# sensors.net
KiCad netlist of a schematic drawn in Altium Designer
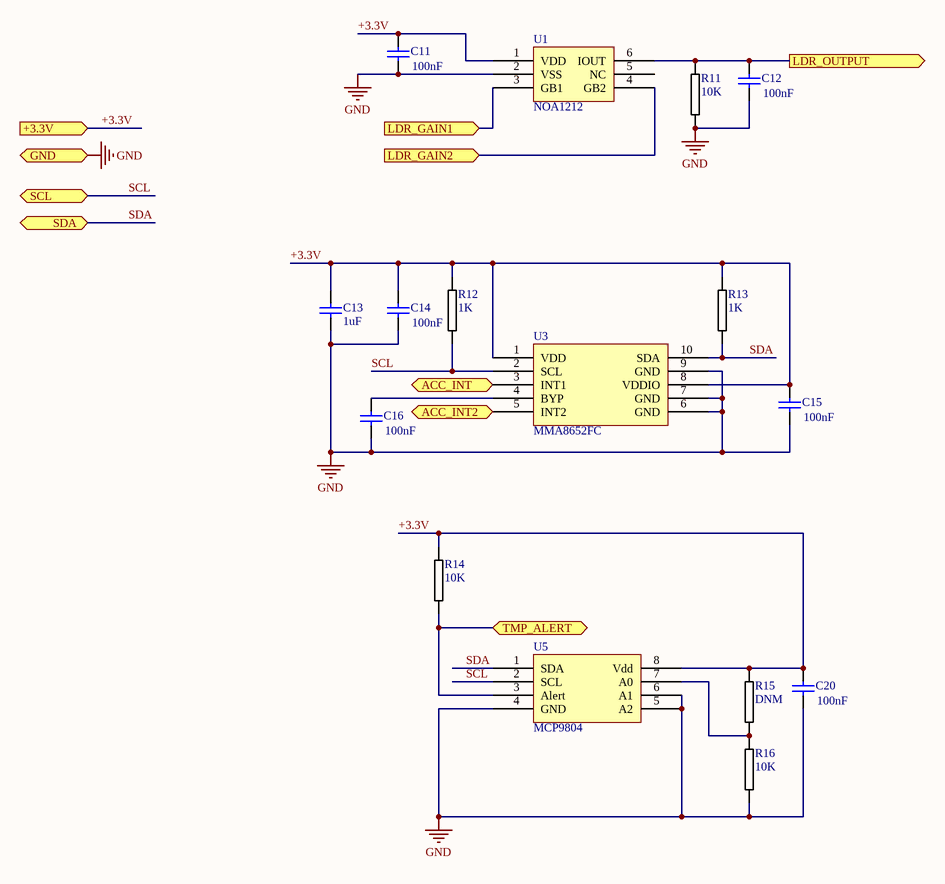
[diagram p0: sensors.SchDoc]

(export (version "E")
  (design (tool "Eeschema 10.0.6"))
  (components
    (comp (ref "C11")
      (value "100nF")
      (footprint "0402C-TBD")
      (description "Capacitor, X7R")
      (libsource (lib "Miscellaneous Devices") (part "Cap"))
    )
    (comp (ref "C12")
      (value "100nF")
      (footprint "0402C-TBD")
      (description "Capacitor, X7R")
      (libsource (lib "Miscellaneous Devices") (part "Cap"))
    )
    (comp (ref "C13")
      (value "1uF")
      (footprint "C0805")
      (description "Capacitor")
      (libsource (lib "Miscellaneous Devices") (part "Cap"))
    )
    (comp (ref "C14")
      (value "100nF")
      (footprint "0402C-TBD")
      (description "Capacitor, X7R")
      (libsource (lib "Miscellaneous Devices") (part "Cap"))
    )
    (comp (ref "C15")
      (value "100nF")
      (footprint "0402C-TBD")
      (description "Capacitor, X7R")
      (libsource (lib "Miscellaneous Devices") (part "Cap"))
    )
    (comp (ref "C16")
      (value "100nF")
      (footprint "0402C-TBD")
      (description "Capacitor, X7R")
      (libsource (lib "Miscellaneous Devices") (part "Cap"))
    )
    (comp (ref "C20")
      (value "100nF")
      (footprint "0402C-TBD")
      (description "Capacitor, X7R")
      (libsource (lib "Miscellaneous Devices") (part "Cap"))
    )
    (comp (ref "R11")
      (value "10K")
      (footprint "0402R-GENERIC")
      (description "RESISTOR 0402 GENERIC")
      (libsource (lib "vh_Altium Library") (part "0402R-GENERIC"))
    )
    (comp (ref "R12")
      (value "1K")
      (footprint "0402R-GENERIC")
      (description "RESISTOR 0402 GENERIC")
      (libsource (lib "vh_Altium Library") (part "0402R-GENERIC"))
    )
    (comp (ref "R13")
      (value "1K")
      (footprint "0402R-GENERIC")
      (description "RESISTOR 0402 GENERIC")
      (libsource (lib "vh_Altium Library") (part "0402R-GENERIC"))
    )
    (comp (ref "R14")
      (value "10K")
      (footprint "0402R-GENERIC")
      (description "RESISTOR 0402 GENERIC")
      (libsource (lib "vh_Altium Library") (part "0402R-GENERIC"))
    )
    (comp (ref "R15")
      (value "DNM")
      (footprint "0402R-GENERIC")
      (description "RESISTOR 0402 GENERIC")
      (libsource (lib "vh_Altium Library") (part "0402R-GENERIC"))
    )
    (comp (ref "R16")
      (value "10K")
      (footprint "0402R-GENERIC")
      (description "RESISTOR 0402 GENERIC")
      (libsource (lib "vh_Altium Library") (part "0402R-GENERIC"))
    )
    (comp (ref "U1") (value "NOA1212") (footprint "NOA1212") (libsource (lib "dell") (part "NOA1212")))
    (comp (ref "U3") (value "MMA8652FC") (footprint "DFN10") (libsource (lib "dell") (part "MMA8652FC")))
    (comp (ref "U5") (value "MCP9804") (footprint "MSOP-MS8_N") (libsource (lib "Schlib1") (part "MCP9804")))
  )
  (nets
    (net (code "1") (name "/+3.3V") (class "Default")
      (node (ref "C11") (pin "2") (pinfunction "2_2") (pintype "passive"))
      (node (ref "C13") (pin "2") (pinfunction "2_2") (pintype "passive"))
      (node (ref "C14") (pin "2") (pinfunction "2_2") (pintype "passive"))
      (node (ref "C15") (pin "2") (pinfunction "2_2") (pintype "passive"))
      (node (ref "C20") (pin "2") (pinfunction "2_2") (pintype "passive"))
      (node (ref "R12") (pin "2") (pintype "passive"))
      (node (ref "R13") (pin "2") (pintype "passive"))
      (node (ref "R14") (pin "2") (pintype "passive"))
      (node (ref "R15") (pin "2") (pintype "passive"))
      (node (ref "U1") (pin "1") (pinfunction "VDD_1") (pintype "passive"))
      (node (ref "U3") (pin "1") (pinfunction "VDD_1") (pintype "passive"))
      (node (ref "U3") (pin "8") (pinfunction "VDDIO_8") (pintype "passive"))
      (node (ref "U5") (pin "8") (pinfunction "Vdd_8") (pintype "passive"))
    )
    (net (code "2") (name "/ACC_INT") (class "Default")
      (node (ref "U3") (pin "3") (pinfunction "INT1_3") (pintype "passive"))
    )
    (net (code "3") (name "/ACC_INT2") (class "Default")
      (node (ref "U3") (pin "5") (pinfunction "INT2_5") (pintype "passive"))
    )
    (net (code "4") (name "/LDR_GAIN1") (class "Default")
      (node (ref "U1") (pin "3") (pinfunction "GB1_3") (pintype "passive"))
    )
    (net (code "5") (name "/LDR_GAIN2") (class "Default")
      (node (ref "U1") (pin "4") (pinfunction "GB2_4") (pintype "passive"))
    )
    (net (code "6") (name "/LDR_OUTPUT") (class "Default")
      (node (ref "C12") (pin "2") (pinfunction "2_2") (pintype "passive"))
      (node (ref "R11") (pin "2") (pintype "passive"))
      (node (ref "U1") (pin "6") (pinfunction "IOUT_6") (pintype "passive"))
    )
    (net (code "7") (name "/SCL") (class "Default")
      (node (ref "R12") (pin "1") (pintype "passive"))
      (node (ref "U3") (pin "2") (pinfunction "SCL_2") (pintype "passive"))
      (node (ref "U5") (pin "2") (pinfunction "SCL_2") (pintype "passive"))
    )
    (net (code "8") (name "/SDA") (class "Default")
      (node (ref "R13") (pin "1") (pintype "passive"))
      (node (ref "U3") (pin "10") (pinfunction "SDA_10") (pintype "passive"))
      (node (ref "U5") (pin "1") (pinfunction "SDA_1") (pintype "passive"))
    )
    (net (code "9") (name "/TMP_ALERT") (class "Default")
      (node (ref "R14") (pin "1") (pintype "passive"))
      (node (ref "U5") (pin "3") (pinfunction "Alert_3") (pintype "passive"))
    )
    (net (code "10") (name "GND") (class "Default")
      (node (ref "C11") (pin "1") (pinfunction "1_1") (pintype "passive"))
      (node (ref "C12") (pin "1") (pinfunction "1_1") (pintype "passive"))
      (node (ref "C13") (pin "1") (pinfunction "1_1") (pintype "passive"))
      (node (ref "C14") (pin "1") (pinfunction "1_1") (pintype "passive"))
      (node (ref "C15") (pin "1") (pinfunction "1_1") (pintype "passive"))
      (node (ref "C16") (pin "1") (pinfunction "1_1") (pintype "passive"))
      (node (ref "C20") (pin "1") (pinfunction "1_1") (pintype "passive"))
      (node (ref "R11") (pin "1") (pintype "passive"))
      (node (ref "R16") (pin "1") (pintype "passive"))
      (node (ref "U1") (pin "2") (pinfunction "VSS_2") (pintype "passive"))
      (node (ref "U3") (pin "6") (pinfunction "GND_6") (pintype "passive"))
      (node (ref "U3") (pin "7") (pinfunction "GND_7") (pintype "passive"))
      (node (ref "U3") (pin "9") (pinfunction "GND_9") (pintype "passive"))
      (node (ref "U5") (pin "4") (pinfunction "GND_4") (pintype "passive"))
      (node (ref "U5") (pin "5") (pinfunction "A2_5") (pintype "passive"))
      (node (ref "U5") (pin "6") (pinfunction "A1_6") (pintype "passive"))
    )
    (net (code "11") (name "Net-(U3-BYP)") (class "Default")
      (node (ref "C16") (pin "2") (pinfunction "2_2") (pintype "passive"))
      (node (ref "U3") (pin "4") (pinfunction "BYP_4") (pintype "passive"))
    )
    (net (code "12") (name "Net-(U5-A0)") (class "Default")
      (node (ref "R15") (pin "1") (pintype "passive"))
      (node (ref "R16") (pin "2") (pintype "passive"))
      (node (ref "U5") (pin "7") (pinfunction "A0_7") (pintype "passive"))
    )
    (net (code "13") (name "unconnected-(U1-NC-Pad5)") (class "Default")
      (node (ref "U1") (pin "5") (pinfunction "NC_5") (pintype "passive"))
    )
  )
)
